# ST_LINK_SWD.net
KiCad netlist of a schematic drawn in Altium Designer
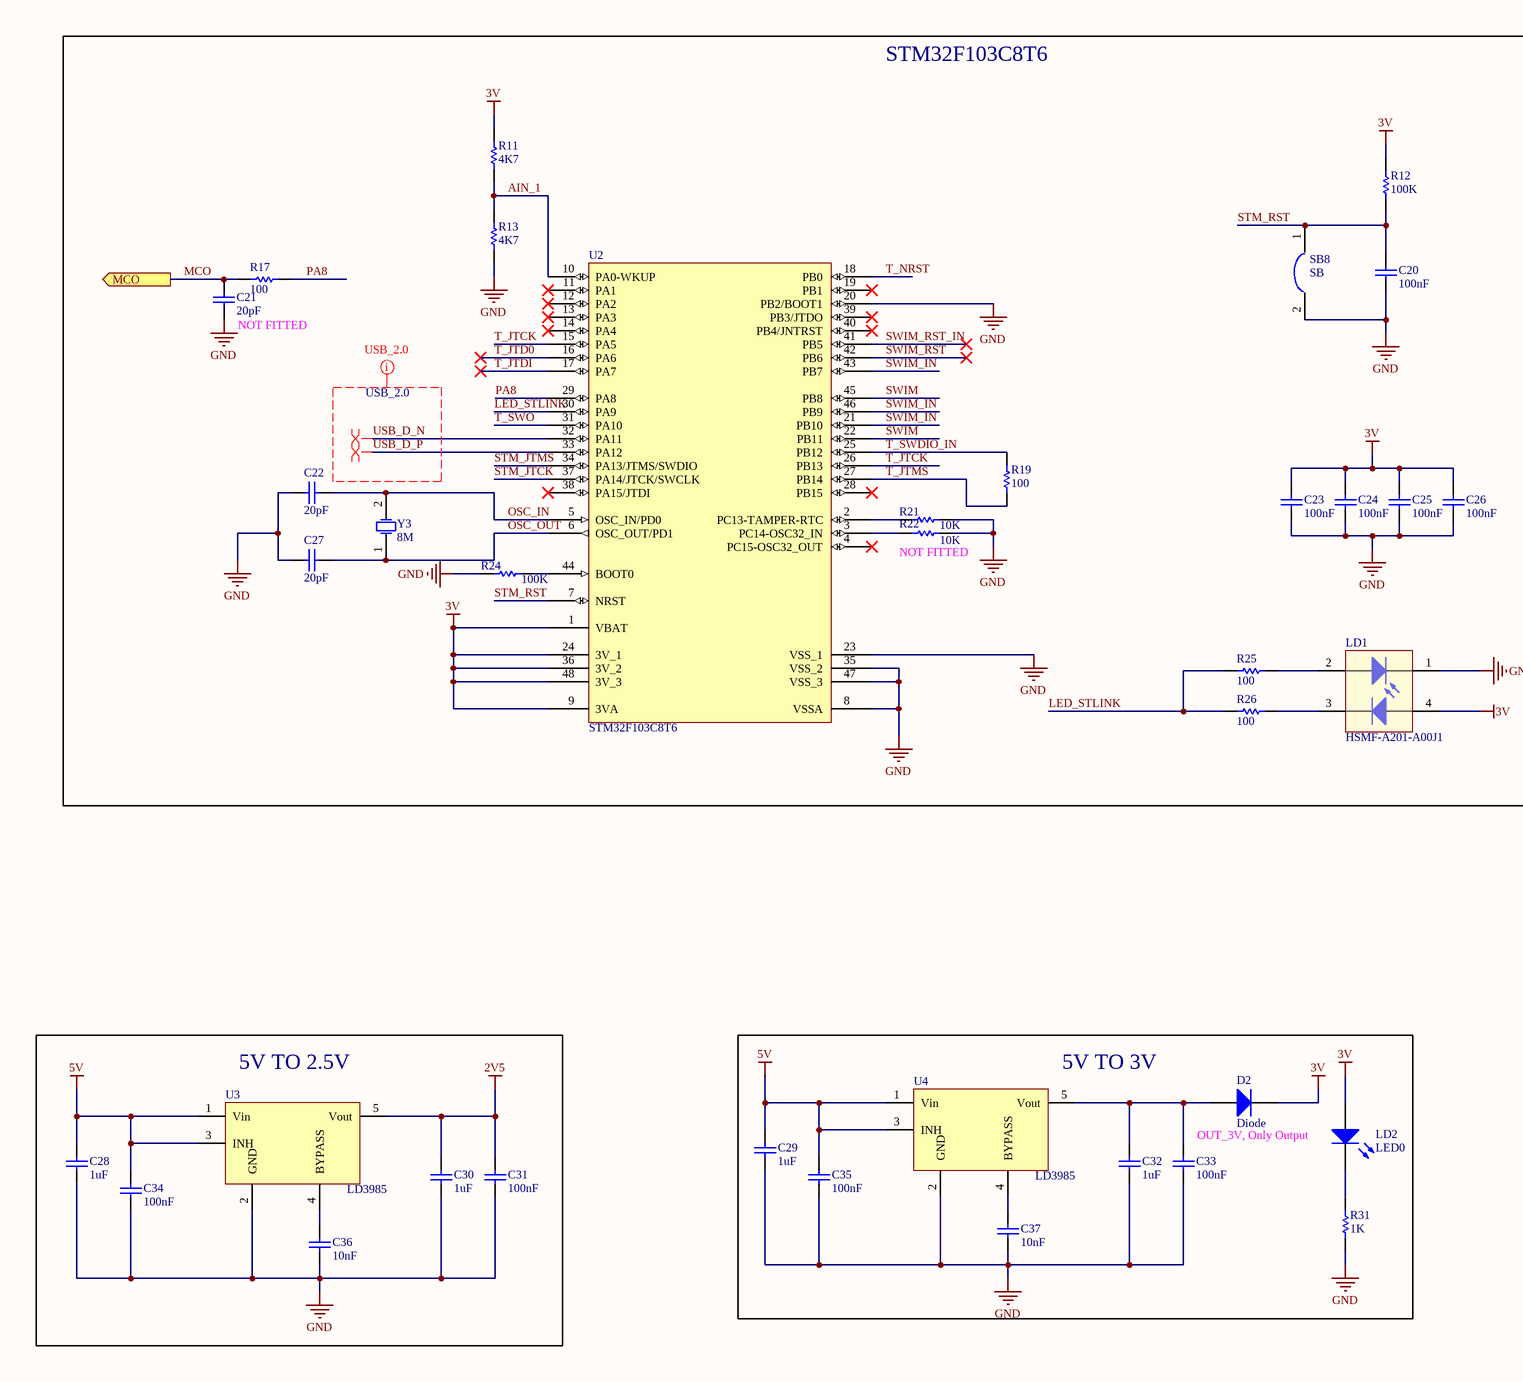
[diagram p0: ST_LINK_SWD.SchDoc, left]
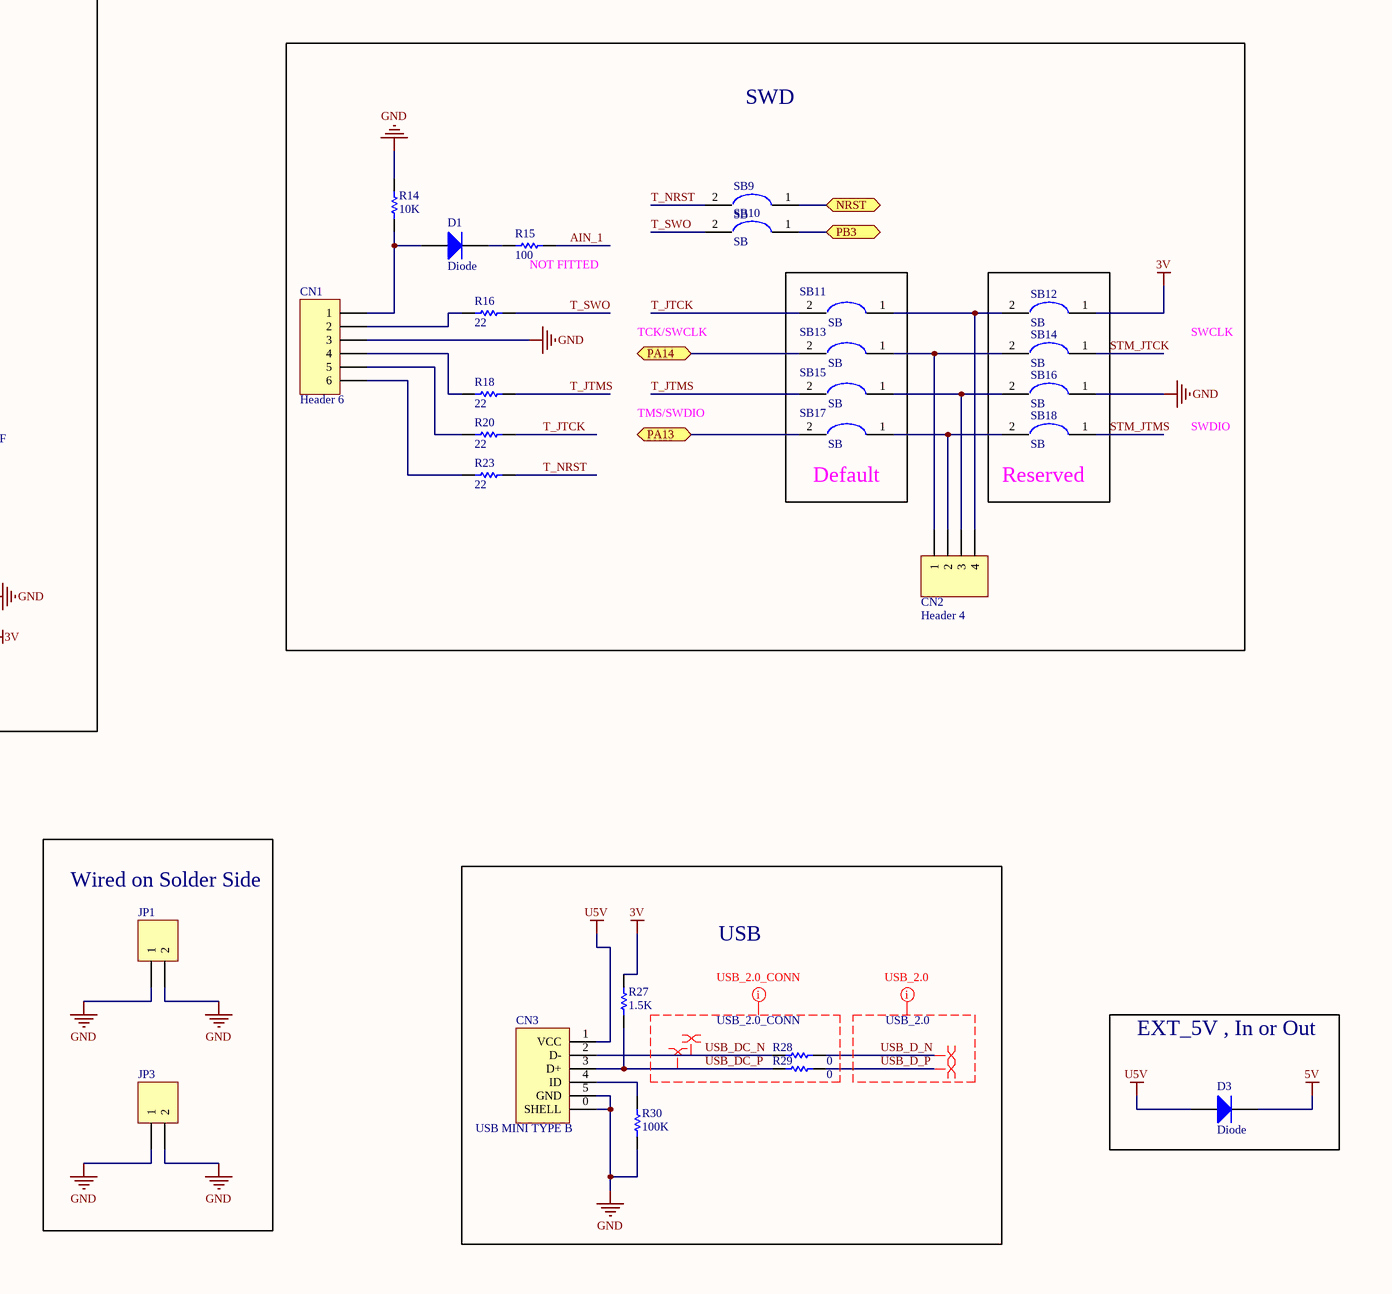
[diagram p1: ST_LINK_SWD.SchDoc, right]

(export (version "E")
  (design (tool "Eeschema 10.0.6"))
  (components
    (comp (ref "C20")
      (value "100nF")
      (footprint "CAPC0603B")
      (description "Capacitor")
      (fields (field (name "Comment") "Cap") (field (name "PUBLISHER") "Altium Limited"))
      (libsource (lib "STM32F4DISCOVERY") (part "Cap_3"))
    )
    (comp (ref "C21")
      (value "20pF")
      (footprint "CAPC0603B")
      (description "Capacitor")
      (fields (field (name "Comment") "Cap") (field (name "PUBLISHER") "Altium Limited"))
      (libsource (lib "STM32F4DISCOVERY") (part "Cap"))
    )
    (comp (ref "C22")
      (value "20pF")
      (footprint "CAPC0603B")
      (description "Capacitor")
      (fields (field (name "Comment") "Cap") (field (name "PUBLISHER") "Altium Limited"))
      (libsource (lib "STM32F4DISCOVERY") (part "Cap"))
    )
    (comp (ref "C23")
      (value "100nF")
      (footprint "CAPC0603B")
      (description "Capacitor")
      (fields (field (name "Comment") "Cap") (field (name "PUBLISHER") "Altium Limited"))
      (libsource (lib "STM32F4DISCOVERY") (part "Cap_3"))
    )
    (comp (ref "C24")
      (value "100nF")
      (footprint "CAPC0603B")
      (description "Capacitor")
      (fields (field (name "Comment") "Cap") (field (name "PUBLISHER") "Altium Limited"))
      (libsource (lib "STM32F4DISCOVERY") (part "Cap_3"))
    )
    (comp (ref "C25")
      (value "100nF")
      (footprint "CAPC0603B")
      (description "Capacitor")
      (fields (field (name "Comment") "Cap") (field (name "PUBLISHER") "Altium Limited"))
      (libsource (lib "STM32F4DISCOVERY") (part "Cap_3"))
    )
    (comp (ref "C26")
      (value "100nF")
      (footprint "CAPC0603B")
      (description "Capacitor")
      (fields (field (name "Comment") "Cap") (field (name "PUBLISHER") "Altium Limited"))
      (libsource (lib "STM32F4DISCOVERY") (part "Cap_3"))
    )
    (comp (ref "C27")
      (value "20pF")
      (footprint "CAPC0603B")
      (description "Capacitor")
      (fields (field (name "Comment") "Cap") (field (name "PUBLISHER") "Altium Limited"))
      (libsource (lib "STM32F4DISCOVERY") (part "Cap"))
    )
    (comp (ref "C28")
      (value "1uF")
      (footprint "CAPC0603B")
      (description "Capacitor")
      (fields (field (name "Comment") "Cap") (field (name "PUBLISHER") "Altium Limited"))
      (libsource (lib "STM32F4DISCOVERY") (part "Cap_4"))
    )
    (comp (ref "C29")
      (value "1uF")
      (footprint "CAPC0603B")
      (description "Capacitor")
      (fields (field (name "Comment") "Cap") (field (name "PUBLISHER") "Altium Limited"))
      (libsource (lib "STM32F4DISCOVERY") (part "Cap_4"))
    )
    (comp (ref "C30")
      (value "1uF")
      (footprint "CAPC0603B")
      (description "Capacitor")
      (fields (field (name "Comment") "Cap") (field (name "PUBLISHER") "Altium Limited"))
      (libsource (lib "STM32F4DISCOVERY") (part "Cap_4"))
    )
    (comp (ref "C31")
      (value "100nF")
      (footprint "CAPC0603B")
      (description "Capacitor")
      (fields (field (name "Comment") "Cap") (field (name "PUBLISHER") "Altium Limited"))
      (libsource (lib "STM32F4DISCOVERY") (part "Cap_3"))
    )
    (comp (ref "C32")
      (value "1uF")
      (footprint "CAPC0603B")
      (description "Capacitor")
      (fields (field (name "Comment") "Cap") (field (name "PUBLISHER") "Altium Limited"))
      (libsource (lib "STM32F4DISCOVERY") (part "Cap_4"))
    )
    (comp (ref "C33")
      (value "100nF")
      (footprint "CAPC0603B")
      (description "Capacitor")
      (fields (field (name "Comment") "Cap") (field (name "PUBLISHER") "Altium Limited"))
      (libsource (lib "STM32F4DISCOVERY") (part "Cap_3"))
    )
    (comp (ref "C34")
      (value "100nF")
      (footprint "CAPC0603B")
      (description "Capacitor")
      (fields (field (name "Comment") "Cap") (field (name "PUBLISHER") "Altium Limited"))
      (libsource (lib "STM32F4DISCOVERY") (part "Cap_3"))
    )
    (comp (ref "C35")
      (value "100nF")
      (footprint "CAPC0603B")
      (description "Capacitor")
      (fields (field (name "Comment") "Cap") (field (name "PUBLISHER") "Altium Limited"))
      (libsource (lib "STM32F4DISCOVERY") (part "Cap_3"))
    )
    (comp (ref "C36")
      (value "10nF")
      (footprint "CAPC0402B")
      (description "Capacitor")
      (fields (field (name "Comment") "Cap") (field (name "PUBLISHER") "Altium Limited"))
      (libsource (lib "STM32F4DISCOVERY") (part "Cap_7"))
    )
    (comp (ref "C37")
      (value "10nF")
      (footprint "CAPC0402B")
      (description "Capacitor")
      (fields (field (name "Comment") "Cap") (field (name "PUBLISHER") "Altium Limited"))
      (libsource (lib "STM32F4DISCOVERY") (part "Cap_7"))
    )
    (comp (ref "CN1")
      (value "Header 6")
      (footprint "HDR1X6")
      (description "Header, 6-Pin")
      (fields (field (name "PUBLISHER") "Altium Limited"))
      (libsource (lib "STM32F4DISCOVERY") (part "Header 6"))
    )
    (comp (ref "CN2")
      (value "Header 4")
      (footprint "HDR1X4")
      (description "Header, 4-Pin")
      (fields (field (name "PUBLISHER") "Altium Limited"))
      (libsource (lib "STM32F4DISCOVERY") (part "Header 4"))
    )
    (comp (ref "CN3")
      (value "USB MINI TYPE B")
      (footprint "STM32FG07VGT6_LIB:USB_MINI_TYPE_B")
      (libsource (lib "SMT32F407VGT6_LIB") (part "USB MINI TYPE B"))
    )
    (comp (ref "D1")
      (value "Diode")
      (footprint "SOD-323")
      (description "Default Diode")
      (fields (field (name "PUBLISHER") "Altium Limited"))
      (libsource (lib "STM32F4DISCOVERY") (part "Diode"))
    )
    (comp (ref "D2")
      (value "Diode")
      (footprint "SOD-323")
      (description "Default Diode")
      (fields (field (name "PUBLISHER") "Altium Limited"))
      (libsource (lib "STM32F4DISCOVERY") (part "Diode"))
    )
    (comp (ref "D3")
      (value "Diode")
      (footprint "SOD-323")
      (description "Default Diode")
      (fields (field (name "PUBLISHER") "Altium Limited"))
      (libsource (lib "STM32F4DISCOVERY") (part "Diode"))
    )
    (comp (ref "JP1")
      (value "Header 2")
      (footprint "HDR1X2")
      (description "Header, 2-Pin")
      (fields (field (name "PUBLISHER") "Altium Limited"))
      (libsource (lib "STM32F4DISCOVERY") (part "Header 2"))
    )
    (comp (ref "JP3")
      (value "Header 2")
      (footprint "HDR1X2")
      (description "Header, 2-Pin")
      (fields (field (name "PUBLISHER") "Altium Limited"))
      (libsource (lib "STM32F4DISCOVERY") (part "Header 2"))
    )
    (comp (ref "LD1")
      (value "HSMF-A201-A00J1")
      (footprint "HSMF-A201-A00J1")
      (fields (field (name "MANUFACTURER") "Broadcom / Avago Technologies"))
      (libsource (lib "STM32F4DISCOVERY") (part "HSMF-A201-A00J1"))
    )
    (comp (ref "LD2")
      (value "LED0")
      (footprint "LED_0603")
      (description "Typical INFRARED GaAs LED")
      (fields (field (name "PUBLISHER") "Altium Limited"))
      (libsource (lib "STM32F4DISCOVERY") (part "LED0"))
    )
    (comp (ref "R11")
      (value "4K7")
      (footprint "RESC0402B")
      (description "Resistor")
      (fields (field (name "Comment") "Res1") (field (name "PUBLISHER") "Altium Limited"))
      (libsource (lib "STM32F4DISCOVERY") (part "Res1_16"))
    )
    (comp (ref "R12")
      (value "100K")
      (footprint "RESC0402B")
      (description "Resistor")
      (fields (field (name "Comment") "Res1") (field (name "PUBLISHER") "Altium Limited"))
      (libsource (lib "STM32F4DISCOVERY") (part "Res1_5"))
    )
    (comp (ref "R13")
      (value "4K7")
      (footprint "RESC0402B")
      (description "Resistor")
      (fields (field (name "Comment") "Res1") (field (name "PUBLISHER") "Altium Limited"))
      (libsource (lib "STM32F4DISCOVERY") (part "Res1_16"))
    )
    (comp (ref "R14")
      (value "10K")
      (footprint "RESC0603B")
      (description "Resistor")
      (fields (field (name "Comment") "Res1") (field (name "PUBLISHER") "Altium Limited"))
      (libsource (lib "STM32F4DISCOVERY") (part "Res1_2"))
    )
    (comp (ref "R15")
      (value "100")
      (footprint "RESC0402B")
      (description "Resistor")
      (fields (field (name "Comment") "Res1") (field (name "PUBLISHER") "Altium Limited"))
      (libsource (lib "STM32F4DISCOVERY") (part "Res1_4"))
    )
    (comp (ref "R16")
      (value "22")
      (footprint "RESC0402B")
      (description "Resistor")
      (fields (field (name "Comment") "Res1") (field (name "PUBLISHER") "Altium Limited"))
      (libsource (lib "STM32F4DISCOVERY") (part "Res1_11"))
    )
    (comp (ref "R17")
      (value "100")
      (footprint "RESC0402B")
      (description "Resistor")
      (fields (field (name "Comment") "Res1") (field (name "PUBLISHER") "Altium Limited"))
      (libsource (lib "STM32F4DISCOVERY") (part "Res1_4"))
    )
    (comp (ref "R18")
      (value "22")
      (footprint "RESC0402B")
      (description "Resistor")
      (fields (field (name "Comment") "Res1") (field (name "PUBLISHER") "Altium Limited"))
      (libsource (lib "STM32F4DISCOVERY") (part "Res1_11"))
    )
    (comp (ref "R19")
      (value "100")
      (footprint "RESC0402B")
      (description "Resistor")
      (fields (field (name "Comment") "Res1") (field (name "PUBLISHER") "Altium Limited"))
      (libsource (lib "STM32F4DISCOVERY") (part "Res1_4"))
    )
    (comp (ref "R20")
      (value "22")
      (footprint "RESC0402B")
      (description "Resistor")
      (fields (field (name "Comment") "Res1") (field (name "PUBLISHER") "Altium Limited"))
      (libsource (lib "STM32F4DISCOVERY") (part "Res1_11"))
    )
    (comp (ref "R21")
      (value "10K")
      (footprint "RESC0603B")
      (description "Resistor")
      (fields (field (name "Comment") "Res1") (field (name "PUBLISHER") "Altium Limited"))
      (libsource (lib "STM32F4DISCOVERY") (part "Res1_2"))
    )
    (comp (ref "R22")
      (value "10K")
      (footprint "RESC0603B")
      (description "Resistor")
      (fields (field (name "Comment") "Res1") (field (name "PUBLISHER") "Altium Limited"))
      (libsource (lib "STM32F4DISCOVERY") (part "Res1_2"))
    )
    (comp (ref "R23")
      (value "22")
      (footprint "RESC0402B")
      (description "Resistor")
      (fields (field (name "Comment") "Res1") (field (name "PUBLISHER") "Altium Limited"))
      (libsource (lib "STM32F4DISCOVERY") (part "Res1_11"))
    )
    (comp (ref "R24")
      (value "100K")
      (footprint "RESC0402B")
      (description "Resistor")
      (fields (field (name "Comment") "Res1") (field (name "PUBLISHER") "Altium Limited"))
      (libsource (lib "STM32F4DISCOVERY") (part "Res1_5"))
    )
    (comp (ref "R25")
      (value "100")
      (footprint "RESC0402B")
      (description "Resistor")
      (fields (field (name "Comment") "Res1") (field (name "PUBLISHER") "Altium Limited"))
      (libsource (lib "STM32F4DISCOVERY") (part "Res1_4"))
    )
    (comp (ref "R26")
      (value "100")
      (footprint "RESC0402B")
      (description "Resistor")
      (fields (field (name "Comment") "Res1") (field (name "PUBLISHER") "Altium Limited"))
      (libsource (lib "STM32F4DISCOVERY") (part "Res1_4"))
    )
    (comp (ref "R27")
      (value "1.5K")
      (footprint "RESC0402B")
      (description "Resistor")
      (fields (field (name "Comment") "Res1") (field (name "PUBLISHER") "Altium Limited"))
      (libsource (lib "STM32F4DISCOVERY") (part "Res1_15"))
    )
    (comp (ref "R28")
      (value "0")
      (footprint "RESC0603B")
      (description "Resistor")
      (fields (field (name "Comment") "Res1") (field (name "PUBLISHER") "Altium Limited"))
      (libsource (lib "STM32F4DISCOVERY") (part "Res1"))
    )
    (comp (ref "R29")
      (value "0")
      (footprint "RESC0603B")
      (description "Resistor")
      (fields (field (name "Comment") "Res1") (field (name "PUBLISHER") "Altium Limited"))
      (libsource (lib "STM32F4DISCOVERY") (part "Res1"))
    )
    (comp (ref "R30")
      (value "100K")
      (footprint "RESC0402B")
      (description "Resistor")
      (fields (field (name "Comment") "Res1") (field (name "PUBLISHER") "Altium Limited"))
      (libsource (lib "STM32F4DISCOVERY") (part "Res1_5"))
    )
    (comp (ref "R31")
      (value "1K")
      (footprint "RESC0402B")
      (description "Resistor")
      (fields (field (name "Comment") "Res1") (field (name "PUBLISHER") "Altium Limited"))
      (libsource (lib "STM32F4DISCOVERY") (part "Res1_17"))
    )
    (comp (ref "SB8") (value "SB") (footprint "SB") (libsource (lib "") (part "SB_1")))
    (comp (ref "SB9") (value "SB") (footprint "SB") (libsource (lib "STM32F4DISCOVERY") (part "SB")))
    (comp (ref "SB10") (value "SB") (footprint "SB") (libsource (lib "STM32F4DISCOVERY") (part "SB")))
    (comp (ref "SB11") (value "SB") (footprint "SB") (libsource (lib "STM32F4DISCOVERY") (part "SB")))
    (comp (ref "SB12") (value "SB") (footprint "SB") (libsource (lib "STM32F4DISCOVERY") (part "SB")))
    (comp (ref "SB13") (value "SB") (footprint "SB") (libsource (lib "STM32F4DISCOVERY") (part "SB")))
    (comp (ref "SB14") (value "SB") (footprint "SB") (libsource (lib "STM32F4DISCOVERY") (part "SB")))
    (comp (ref "SB15") (value "SB") (footprint "SB") (libsource (lib "STM32F4DISCOVERY") (part "SB")))
    (comp (ref "SB16") (value "SB") (footprint "SB") (libsource (lib "STM32F4DISCOVERY") (part "SB")))
    (comp (ref "SB17") (value "SB") (footprint "SB") (libsource (lib "STM32F4DISCOVERY") (part "SB")))
    (comp (ref "SB18") (value "SB") (footprint "SB") (libsource (lib "STM32F4DISCOVERY") (part "SB")))
    (comp (ref "U2")
      (value "STM32F103C8T6")
      (footprint "LQFP48_N")
      (description "STM32 ARM-based 32-bit MCU with 64 Kbytes Flash, 48-pin LQFP, Industrial Temperature")
      (fields (field (name "PUBLISHER") "Altium Limited"))
      (libsource (lib "STM32F4DISCOVERY") (part "STM32F103C8T6"))
    )
    (comp (ref "U3")
      (value "LD3985")
      (footprint "TSOT-23-5")
      (fields
        (field (name "MANUFACTURER") "STMicroelectronics")
        (field (name "MANUFACTURER PART NUMBER") "LD3985G33R")
      )
      (libsource (lib "STM32F4DISCOVERY") (part "LD3985"))
    )
    (comp (ref "U4")
      (value "LD3985")
      (footprint "TSOT-23-5")
      (fields
        (field (name "MANUFACTURER") "STMicroelectronics")
        (field (name "MANUFACTURER PART NUMBER") "LD3985G33R")
      )
      (libsource (lib "STM32F4DISCOVERY") (part "LD3985"))
    )
    (comp (ref "Y3")
      (value "8M")
      (footprint "HC-49S")
      (description "Crystal Oscillator")
      (fields (field (name "PUBLISHER") "Altium Limited"))
      (libsource (lib "STM32F4DISCOVERY") (part "XTAL"))
    )
  )
  (nets
    (net (code "1") (name "/AIN_1") (class "Default")
      (node (ref "R11") (pin "1") (pinfunction "1_1") (pintype "passive"))
      (node (ref "R13") (pin "2") (pinfunction "2_2") (pintype "passive"))
      (node (ref "R15") (pin "1") (pinfunction "1_1") (pintype "passive"))
      (node (ref "U2") (pin "10") (pinfunction "PA0-WKUP_10") (pintype "bidirectional"))
    )
    (net (code "2") (name "/LED_STLINK") (class "Default")
      (node (ref "R25") (pin "2") (pinfunction "2_2") (pintype "passive"))
      (node (ref "R26") (pin "2") (pinfunction "2_2") (pintype "passive"))
      (node (ref "U2") (pin "30") (pinfunction "PA9_30") (pintype "bidirectional"))
    )
    (net (code "3") (name "/MCO") (class "Default")
      (node (ref "C21") (pin "2") (pinfunction "2_2") (pintype "passive"))
      (node (ref "R17") (pin "2") (pinfunction "2_2") (pintype "passive"))
    )
    (net (code "4") (name "/NRST") (class "Default")
      (node (ref "SB9") (pin "1") (pinfunction "1_1") (pintype "passive"))
    )
    (net (code "5") (name "/OSC_IN") (class "Default")
      (node (ref "C22") (pin "2") (pinfunction "2_2") (pintype "passive"))
      (node (ref "U2") (pin "5") (pinfunction "OSC_IN/PD0_5") (pintype "input"))
      (node (ref "Y3") (pin "2") (pinfunction "OSC2_2") (pintype "passive"))
    )
    (net (code "6") (name "/OSC_OUT") (class "Default")
      (node (ref "C27") (pin "2") (pinfunction "2_2") (pintype "passive"))
      (node (ref "U2") (pin "6") (pinfunction "OSC_OUT/PD1_6") (pintype "output"))
      (node (ref "Y3") (pin "1") (pinfunction "OSC1_1") (pintype "passive"))
    )
    (net (code "7") (name "/PA8") (class "Default")
      (node (ref "R17") (pin "1") (pinfunction "1_1") (pintype "passive"))
      (node (ref "U2") (pin "29") (pinfunction "PA8_29") (pintype "bidirectional"))
    )
    (net (code "8") (name "/PA13") (class "Default")
      (node (ref "SB17") (pin "2") (pinfunction "2_2") (pintype "passive"))
    )
    (net (code "9") (name "/PA14") (class "Default")
      (node (ref "SB13") (pin "2") (pinfunction "2_2") (pintype "passive"))
    )
    (net (code "10") (name "/PB3") (class "Default")
      (node (ref "SB10") (pin "1") (pinfunction "1_1") (pintype "passive"))
    )
    (net (code "11") (name "/STM_JTCK") (class "Default")
      (node (ref "SB14") (pin "1") (pinfunction "1_1") (pintype "passive"))
      (node (ref "U2") (pin "37") (pinfunction "PA14/JTCK/SWCLK_37") (pintype "bidirectional"))
    )
    (net (code "12") (name "/STM_JTMS") (class "Default")
      (node (ref "SB18") (pin "1") (pinfunction "1_1") (pintype "passive"))
      (node (ref "U2") (pin "34") (pinfunction "PA13/JTMS/SWDIO_34") (pintype "bidirectional"))
    )
    (net (code "13") (name "/STM_RST") (class "Default")
      (node (ref "C20") (pin "2") (pinfunction "2_2") (pintype "passive"))
      (node (ref "R12") (pin "2") (pinfunction "2_2") (pintype "passive"))
      (node (ref "SB8") (pin "1") (pinfunction "1_1") (pintype "passive"))
      (node (ref "U2") (pin "7") (pinfunction "NRST_7") (pintype "bidirectional"))
    )
    (net (code "14") (name "/SWIM") (class "Default")
      (node (ref "U2") (pin "22") (pinfunction "PB11_22") (pintype "bidirectional"))
      (node (ref "U2") (pin "45") (pinfunction "PB8_45") (pintype "bidirectional"))
    )
    (net (code "15") (name "/SWIM_IN") (class "Default")
      (node (ref "U2") (pin "21") (pinfunction "PB10_21") (pintype "bidirectional"))
      (node (ref "U2") (pin "43") (pinfunction "PB7_43") (pintype "bidirectional"))
      (node (ref "U2") (pin "46") (pinfunction "PB9_46") (pintype "bidirectional"))
    )
    (net (code "16") (name "/SWIM_RST") (class "Default")
      (node (ref "U2") (pin "42") (pinfunction "PB6_42") (pintype "bidirectional+no_connect"))
    )
    (net (code "17") (name "/SWIM_RST_IN") (class "Default")
      (node (ref "U2") (pin "41") (pinfunction "PB5_41") (pintype "bidirectional+no_connect"))
    )
    (net (code "18") (name "/T_JTCK") (class "Default")
      (node (ref "R20") (pin "2") (pinfunction "2_2") (pintype "passive"))
      (node (ref "SB11") (pin "2") (pinfunction "2_2") (pintype "passive"))
      (node (ref "U2") (pin "15") (pinfunction "PA5_15") (pintype "bidirectional"))
      (node (ref "U2") (pin "26") (pinfunction "PB13_26") (pintype "bidirectional"))
    )
    (net (code "19") (name "/T_JTD0") (class "Default")
      (node (ref "U2") (pin "16") (pinfunction "PA6_16") (pintype "bidirectional+no_connect"))
    )
    (net (code "20") (name "/T_JTDI") (class "Default")
      (node (ref "U2") (pin "17") (pinfunction "PA7_17") (pintype "bidirectional+no_connect"))
    )
    (net (code "21") (name "/T_JTMS") (class "Default")
      (node (ref "R18") (pin "2") (pinfunction "2_2") (pintype "passive"))
      (node (ref "R19") (pin "1") (pinfunction "1_1") (pintype "passive"))
      (node (ref "SB15") (pin "2") (pinfunction "2_2") (pintype "passive"))
      (node (ref "U2") (pin "27") (pinfunction "PB14_27") (pintype "bidirectional"))
    )
    (net (code "22") (name "/T_NRST") (class "Default")
      (node (ref "R23") (pin "2") (pinfunction "2_2") (pintype "passive"))
      (node (ref "SB9") (pin "2") (pinfunction "2_2") (pintype "passive"))
      (node (ref "U2") (pin "18") (pinfunction "PB0_18") (pintype "bidirectional"))
    )
    (net (code "23") (name "/T_SWDIO_IN") (class "Default")
      (node (ref "R19") (pin "2") (pinfunction "2_2") (pintype "passive"))
      (node (ref "U2") (pin "25") (pinfunction "PB12_25") (pintype "bidirectional"))
    )
    (net (code "24") (name "/T_SWO") (class "Default")
      (node (ref "R16") (pin "2") (pinfunction "2_2") (pintype "passive"))
      (node (ref "SB10") (pin "2") (pinfunction "2_2") (pintype "passive"))
      (node (ref "U2") (pin "31") (pinfunction "PA10_31") (pintype "bidirectional"))
    )
    (net (code "25") (name "/USB_DC_N") (class "Default")
      (node (ref "CN3") (pin "2") (pinfunction "D-_2") (pintype "passive"))
      (node (ref "R28") (pin "1") (pinfunction "1_1") (pintype "passive"))
    )
    (net (code "26") (name "/USB_DC_P") (class "Default")
      (node (ref "CN3") (pin "3") (pinfunction "D+_3") (pintype "passive"))
      (node (ref "R27") (pin "1") (pinfunction "1_1") (pintype "passive"))
      (node (ref "R29") (pin "1") (pinfunction "1_1") (pintype "passive"))
    )
    (net (code "27") (name "/USB_D_N") (class "Default")
      (node (ref "R28") (pin "2") (pinfunction "2_2") (pintype "passive"))
      (node (ref "U2") (pin "32") (pinfunction "PA11_32") (pintype "bidirectional"))
    )
    (net (code "28") (name "/USB_D_P") (class "Default")
      (node (ref "R29") (pin "2") (pinfunction "2_2") (pintype "passive"))
      (node (ref "U2") (pin "33") (pinfunction "PA12_33") (pintype "bidirectional"))
    )
    (net (code "29") (name "2V5") (class "Default")
      (node (ref "C30") (pin "2") (pinfunction "2_2") (pintype "passive"))
      (node (ref "C31") (pin "2") (pinfunction "2_2") (pintype "passive"))
      (node (ref "U3") (pin "5") (pinfunction "Vout_5") (pintype "passive"))
    )
    (net (code "30") (name "3V") (class "Default")
      (node (ref "C23") (pin "2") (pinfunction "2_2") (pintype "passive"))
      (node (ref "C24") (pin "2") (pinfunction "2_2") (pintype "passive"))
      (node (ref "C25") (pin "2") (pinfunction "2_2") (pintype "passive"))
      (node (ref "C26") (pin "2") (pinfunction "2_2") (pintype "passive"))
      (node (ref "D2") (pin "2") (pinfunction "K_2") (pintype "passive"))
      (node (ref "LD1") (pin "4") (pinfunction "4_4") (pintype "passive"))
      (node (ref "LD2") (pin "1") (pinfunction "A_1") (pintype "passive"))
      (node (ref "R11") (pin "2") (pinfunction "2_2") (pintype "passive"))
      (node (ref "R12") (pin "1") (pinfunction "1_1") (pintype "passive"))
      (node (ref "R27") (pin "2") (pinfunction "2_2") (pintype "passive"))
      (node (ref "SB12") (pin "1") (pinfunction "1_1") (pintype "passive"))
      (node (ref "U2") (pin "1") (pinfunction "VBAT_1") (pintype "power_in"))
      (node (ref "U2") (pin "24") (pinfunction "3V_1_24") (pintype "power_in"))
      (node (ref "U2") (pin "36") (pinfunction "3V_2_36") (pintype "power_in"))
      (node (ref "U2") (pin "48") (pinfunction "3V_3_48") (pintype "power_in"))
      (node (ref "U2") (pin "9") (pinfunction "3VA_9") (pintype "power_in"))
    )
    (net (code "31") (name "5V") (class "Default")
      (node (ref "C28") (pin "2") (pinfunction "2_2") (pintype "passive"))
      (node (ref "C29") (pin "2") (pinfunction "2_2") (pintype "passive"))
      (node (ref "C34") (pin "2") (pinfunction "2_2") (pintype "passive"))
      (node (ref "C35") (pin "2") (pinfunction "2_2") (pintype "passive"))
      (node (ref "D3") (pin "2") (pinfunction "K_2") (pintype "passive"))
      (node (ref "U3") (pin "1") (pinfunction "Vin_1") (pintype "passive"))
      (node (ref "U3") (pin "3") (pinfunction "INH_3") (pintype "passive"))
      (node (ref "U4") (pin "1") (pinfunction "Vin_1") (pintype "passive"))
      (node (ref "U4") (pin "3") (pinfunction "INH_3") (pintype "passive"))
    )
    (net (code "32") (name "GND") (class "Default")
      (node (ref "C20") (pin "1") (pinfunction "1_1") (pintype "passive"))
      (node (ref "C21") (pin "1") (pinfunction "1_1") (pintype "passive"))
      (node (ref "C22") (pin "1") (pinfunction "1_1") (pintype "passive"))
      (node (ref "C23") (pin "1") (pinfunction "1_1") (pintype "passive"))
      (node (ref "C24") (pin "1") (pinfunction "1_1") (pintype "passive"))
      (node (ref "C25") (pin "1") (pinfunction "1_1") (pintype "passive"))
      (node (ref "C26") (pin "1") (pinfunction "1_1") (pintype "passive"))
      (node (ref "C27") (pin "1") (pinfunction "1_1") (pintype "passive"))
      (node (ref "C28") (pin "1") (pinfunction "1_1") (pintype "passive"))
      (node (ref "C29") (pin "1") (pinfunction "1_1") (pintype "passive"))
      (node (ref "C30") (pin "1") (pinfunction "1_1") (pintype "passive"))
      (node (ref "C31") (pin "1") (pinfunction "1_1") (pintype "passive"))
      (node (ref "C32") (pin "1") (pinfunction "1_1") (pintype "passive"))
      (node (ref "C33") (pin "1") (pinfunction "1_1") (pintype "passive"))
      (node (ref "C34") (pin "1") (pinfunction "1_1") (pintype "passive"))
      (node (ref "C35") (pin "1") (pinfunction "1_1") (pintype "passive"))
      (node (ref "C36") (pin "1") (pinfunction "1_1") (pintype "passive"))
      (node (ref "C37") (pin "1") (pinfunction "1_1") (pintype "passive"))
      (node (ref "CN1") (pin "3") (pinfunction "3_3") (pintype "passive"))
      (node (ref "CN3") (pin "0") (pinfunction "SHELL_0") (pintype "passive"))
      (node (ref "CN3") (pin "5") (pinfunction "GND_5") (pintype "passive"))
      (node (ref "JP1") (pin "1") (pinfunction "1_1") (pintype "passive"))
      (node (ref "JP1") (pin "2") (pinfunction "2_2") (pintype "passive"))
      (node (ref "JP3") (pin "1") (pinfunction "1_1") (pintype "passive"))
      (node (ref "JP3") (pin "2") (pinfunction "2_2") (pintype "passive"))
      (node (ref "LD1") (pin "1") (pinfunction "1_1") (pintype "passive"))
      (node (ref "R13") (pin "1") (pinfunction "1_1") (pintype "passive"))
      (node (ref "R14") (pin "2") (pinfunction "2_2") (pintype "passive"))
      (node (ref "R21") (pin "2") (pinfunction "2_2") (pintype "passive"))
      (node (ref "R22") (pin "2") (pinfunction "2_2") (pintype "passive"))
      (node (ref "R24") (pin "1") (pinfunction "1_1") (pintype "passive"))
      (node (ref "R30") (pin "2") (pinfunction "2_2") (pintype "passive"))
      (node (ref "R31") (pin "1") (pinfunction "1_1") (pintype "passive"))
      (node (ref "SB16") (pin "1") (pinfunction "1_1") (pintype "passive"))
      (node (ref "SB8") (pin "2") (pinfunction "2_2") (pintype "passive"))
      (node (ref "U2") (pin "20") (pinfunction "PB2/BOOT1_20") (pintype "bidirectional"))
      (node (ref "U2") (pin "23") (pinfunction "VSS_1_23") (pintype "power_in"))
      (node (ref "U2") (pin "35") (pinfunction "VSS_2_35") (pintype "power_in"))
      (node (ref "U2") (pin "47") (pinfunction "VSS_3_47") (pintype "power_in"))
      (node (ref "U2") (pin "8") (pinfunction "VSSA_8") (pintype "power_in"))
      (node (ref "U3") (pin "2") (pinfunction "GND_2") (pintype "passive"))
      (node (ref "U4") (pin "2") (pinfunction "GND_2") (pintype "passive"))
    )
    (net (code "33") (name "Net-(CN1-Pad2)") (class "Default")
      (node (ref "CN1") (pin "2") (pinfunction "2_2") (pintype "passive"))
      (node (ref "R16") (pin "1") (pinfunction "1_1") (pintype "passive"))
    )
    (net (code "34") (name "Net-(CN1-Pad4)") (class "Default")
      (node (ref "CN1") (pin "4") (pinfunction "4_4") (pintype "passive"))
      (node (ref "R18") (pin "1") (pinfunction "1_1") (pintype "passive"))
    )
    (net (code "35") (name "Net-(CN1-Pad5)") (class "Default")
      (node (ref "CN1") (pin "5") (pinfunction "5_5") (pintype "passive"))
      (node (ref "R20") (pin "1") (pinfunction "1_1") (pintype "passive"))
    )
    (net (code "36") (name "Net-(CN1-Pad6)") (class "Default")
      (node (ref "CN1") (pin "6") (pinfunction "6_6") (pintype "passive"))
      (node (ref "R23") (pin "1") (pinfunction "1_1") (pintype "passive"))
    )
    (net (code "37") (name "Net-(CN2-Pad1)") (class "Default")
      (node (ref "CN2") (pin "1") (pinfunction "1_1") (pintype "passive"))
      (node (ref "SB13") (pin "1") (pinfunction "1_1") (pintype "passive"))
      (node (ref "SB14") (pin "2") (pinfunction "2_2") (pintype "passive"))
    )
    (net (code "38") (name "Net-(CN2-Pad2)") (class "Default")
      (node (ref "CN2") (pin "2") (pinfunction "2_2") (pintype "passive"))
      (node (ref "SB17") (pin "1") (pinfunction "1_1") (pintype "passive"))
      (node (ref "SB18") (pin "2") (pinfunction "2_2") (pintype "passive"))
    )
    (net (code "39") (name "Net-(CN2-Pad3)") (class "Default")
      (node (ref "CN2") (pin "3") (pinfunction "3_3") (pintype "passive"))
      (node (ref "SB15") (pin "1") (pinfunction "1_1") (pintype "passive"))
      (node (ref "SB16") (pin "2") (pinfunction "2_2") (pintype "passive"))
    )
    (net (code "40") (name "Net-(CN2-Pad4)") (class "Default")
      (node (ref "CN2") (pin "4") (pinfunction "4_4") (pintype "passive"))
      (node (ref "SB11") (pin "1") (pinfunction "1_1") (pintype "passive"))
      (node (ref "SB12") (pin "2") (pinfunction "2_2") (pintype "passive"))
    )
    (net (code "41") (name "Net-(CN3-ID)") (class "Default")
      (node (ref "CN3") (pin "4") (pinfunction "ID_4") (pintype "passive"))
      (node (ref "R30") (pin "1") (pinfunction "1_1") (pintype "passive"))
    )
    (net (code "42") (name "Net-(D1-A)") (class "Default")
      (node (ref "CN1") (pin "1") (pinfunction "1_1") (pintype "passive"))
      (node (ref "D1") (pin "1") (pinfunction "A_1") (pintype "passive"))
      (node (ref "R14") (pin "1") (pinfunction "1_1") (pintype "passive"))
    )
    (net (code "43") (name "Net-(D1-K)") (class "Default")
      (node (ref "D1") (pin "2") (pinfunction "K_2") (pintype "passive"))
      (node (ref "R15") (pin "2") (pinfunction "2_2") (pintype "passive"))
    )
    (net (code "44") (name "Net-(D2-A)") (class "Default")
      (node (ref "C32") (pin "2") (pinfunction "2_2") (pintype "passive"))
      (node (ref "C33") (pin "2") (pinfunction "2_2") (pintype "passive"))
      (node (ref "D2") (pin "1") (pinfunction "A_1") (pintype "passive"))
      (node (ref "U4") (pin "5") (pinfunction "Vout_5") (pintype "passive"))
    )
    (net (code "45") (name "Net-(LD1-Pad2)") (class "Default")
      (node (ref "LD1") (pin "2") (pinfunction "2_2") (pintype "passive"))
      (node (ref "R25") (pin "1") (pinfunction "1_1") (pintype "passive"))
    )
    (net (code "46") (name "Net-(LD1-Pad3)") (class "Default")
      (node (ref "LD1") (pin "3") (pinfunction "3_3") (pintype "passive"))
      (node (ref "R26") (pin "1") (pinfunction "1_1") (pintype "passive"))
    )
    (net (code "47") (name "Net-(LD2-K)") (class "Default")
      (node (ref "LD2") (pin "2") (pinfunction "K_2") (pintype "passive"))
      (node (ref "R31") (pin "2") (pinfunction "2_2") (pintype "passive"))
    )
    (net (code "48") (name "Net-(U2-BOOT0)") (class "Default")
      (node (ref "R24") (pin "2") (pinfunction "2_2") (pintype "passive"))
      (node (ref "U2") (pin "44") (pinfunction "BOOT0_44") (pintype "input"))
    )
    (net (code "49") (name "Net-(U2-PC13-TAMPER-RTC)") (class "Default")
      (node (ref "R21") (pin "1") (pinfunction "1_1") (pintype "passive"))
      (node (ref "U2") (pin "2") (pinfunction "PC13-TAMPER-RTC_2") (pintype "bidirectional"))
    )
    (net (code "50") (name "Net-(U2-PC14-OSC32_IN)") (class "Default")
      (node (ref "R22") (pin "1") (pinfunction "1_1") (pintype "passive"))
      (node (ref "U2") (pin "3") (pinfunction "PC14-OSC32_IN_3") (pintype "bidirectional"))
    )
    (net (code "51") (name "Net-(U3-BYPASS)") (class "Default")
      (node (ref "C36") (pin "2") (pinfunction "2_2") (pintype "passive"))
      (node (ref "U3") (pin "4") (pinfunction "BYPASS_4") (pintype "passive"))
    )
    (net (code "52") (name "Net-(U4-BYPASS)") (class "Default")
      (node (ref "C37") (pin "2") (pinfunction "2_2") (pintype "passive"))
      (node (ref "U4") (pin "4") (pinfunction "BYPASS_4") (pintype "passive"))
    )
    (net (code "53") (name "U5V") (class "Default")
      (node (ref "CN3") (pin "1") (pinfunction "VCC_1") (pintype "passive"))
      (node (ref "D3") (pin "1") (pinfunction "A_1") (pintype "passive"))
    )
    (net (code "54") (name "unconnected-(LD1-A-Pad1)") (class "Default")
      (node (ref "LD1") (pin "1") (pinfunction "A_1") (pintype "passive"))
    )
    (net (code "55") (name "unconnected-(LD1-A-Pad1)_1") (class "Default")
      (node (ref "LD1") (pin "1") (pinfunction "A_1") (pintype "passive"))
    )
    (net (code "56") (name "unconnected-(LD1-K-Pad2)") (class "Default")
      (node (ref "LD1") (pin "2") (pinfunction "K_2") (pintype "passive"))
    )
    (net (code "57") (name "unconnected-(LD1-K-Pad2)_1") (class "Default")
      (node (ref "LD1") (pin "2") (pinfunction "K_2") (pintype "passive"))
    )
    (net (code "58") (name "unconnected-(U2-PA1-Pad11)") (class "Default")
      (node (ref "U2") (pin "11") (pinfunction "PA1_11") (pintype "bidirectional+no_connect"))
    )
    (net (code "59") (name "unconnected-(U2-PA2-Pad12)") (class "Default")
      (node (ref "U2") (pin "12") (pinfunction "PA2_12") (pintype "bidirectional+no_connect"))
    )
    (net (code "60") (name "unconnected-(U2-PA3-Pad13)") (class "Default")
      (node (ref "U2") (pin "13") (pinfunction "PA3_13") (pintype "bidirectional+no_connect"))
    )
    (net (code "61") (name "unconnected-(U2-PA4-Pad14)") (class "Default")
      (node (ref "U2") (pin "14") (pinfunction "PA4_14") (pintype "bidirectional+no_connect"))
    )
    (net (code "62") (name "unconnected-(U2-PA15{slash}JTDI-Pad38)") (class "Default")
      (node (ref "U2") (pin "38") (pinfunction "PA15/JTDI_38") (pintype "bidirectional+no_connect"))
    )
    (net (code "63") (name "unconnected-(U2-PB1-Pad19)") (class "Default")
      (node (ref "U2") (pin "19") (pinfunction "PB1_19") (pintype "bidirectional+no_connect"))
    )
    (net (code "64") (name "unconnected-(U2-PB3{slash}JTDO-Pad39)") (class "Default")
      (node (ref "U2") (pin "39") (pinfunction "PB3/JTDO_39") (pintype "bidirectional+no_connect"))
    )
    (net (code "65") (name "unconnected-(U2-PB4{slash}JNTRST-Pad40)") (class "Default")
      (node (ref "U2") (pin "40") (pinfunction "PB4/JNTRST_40") (pintype "bidirectional+no_connect"))
    )
    (net (code "66") (name "unconnected-(U2-PB15-Pad28)") (class "Default")
      (node (ref "U2") (pin "28") (pinfunction "PB15_28") (pintype "bidirectional+no_connect"))
    )
    (net (code "67") (name "unconnected-(U2-PC15-OSC32_OUT-Pad4)") (class "Default")
      (node (ref "U2") (pin "4") (pinfunction "PC15-OSC32_OUT_4") (pintype "bidirectional+no_connect"))
    )
  )
)
